# Qiao.net
KiCad netlist of a schematic drawn in Altium Designer
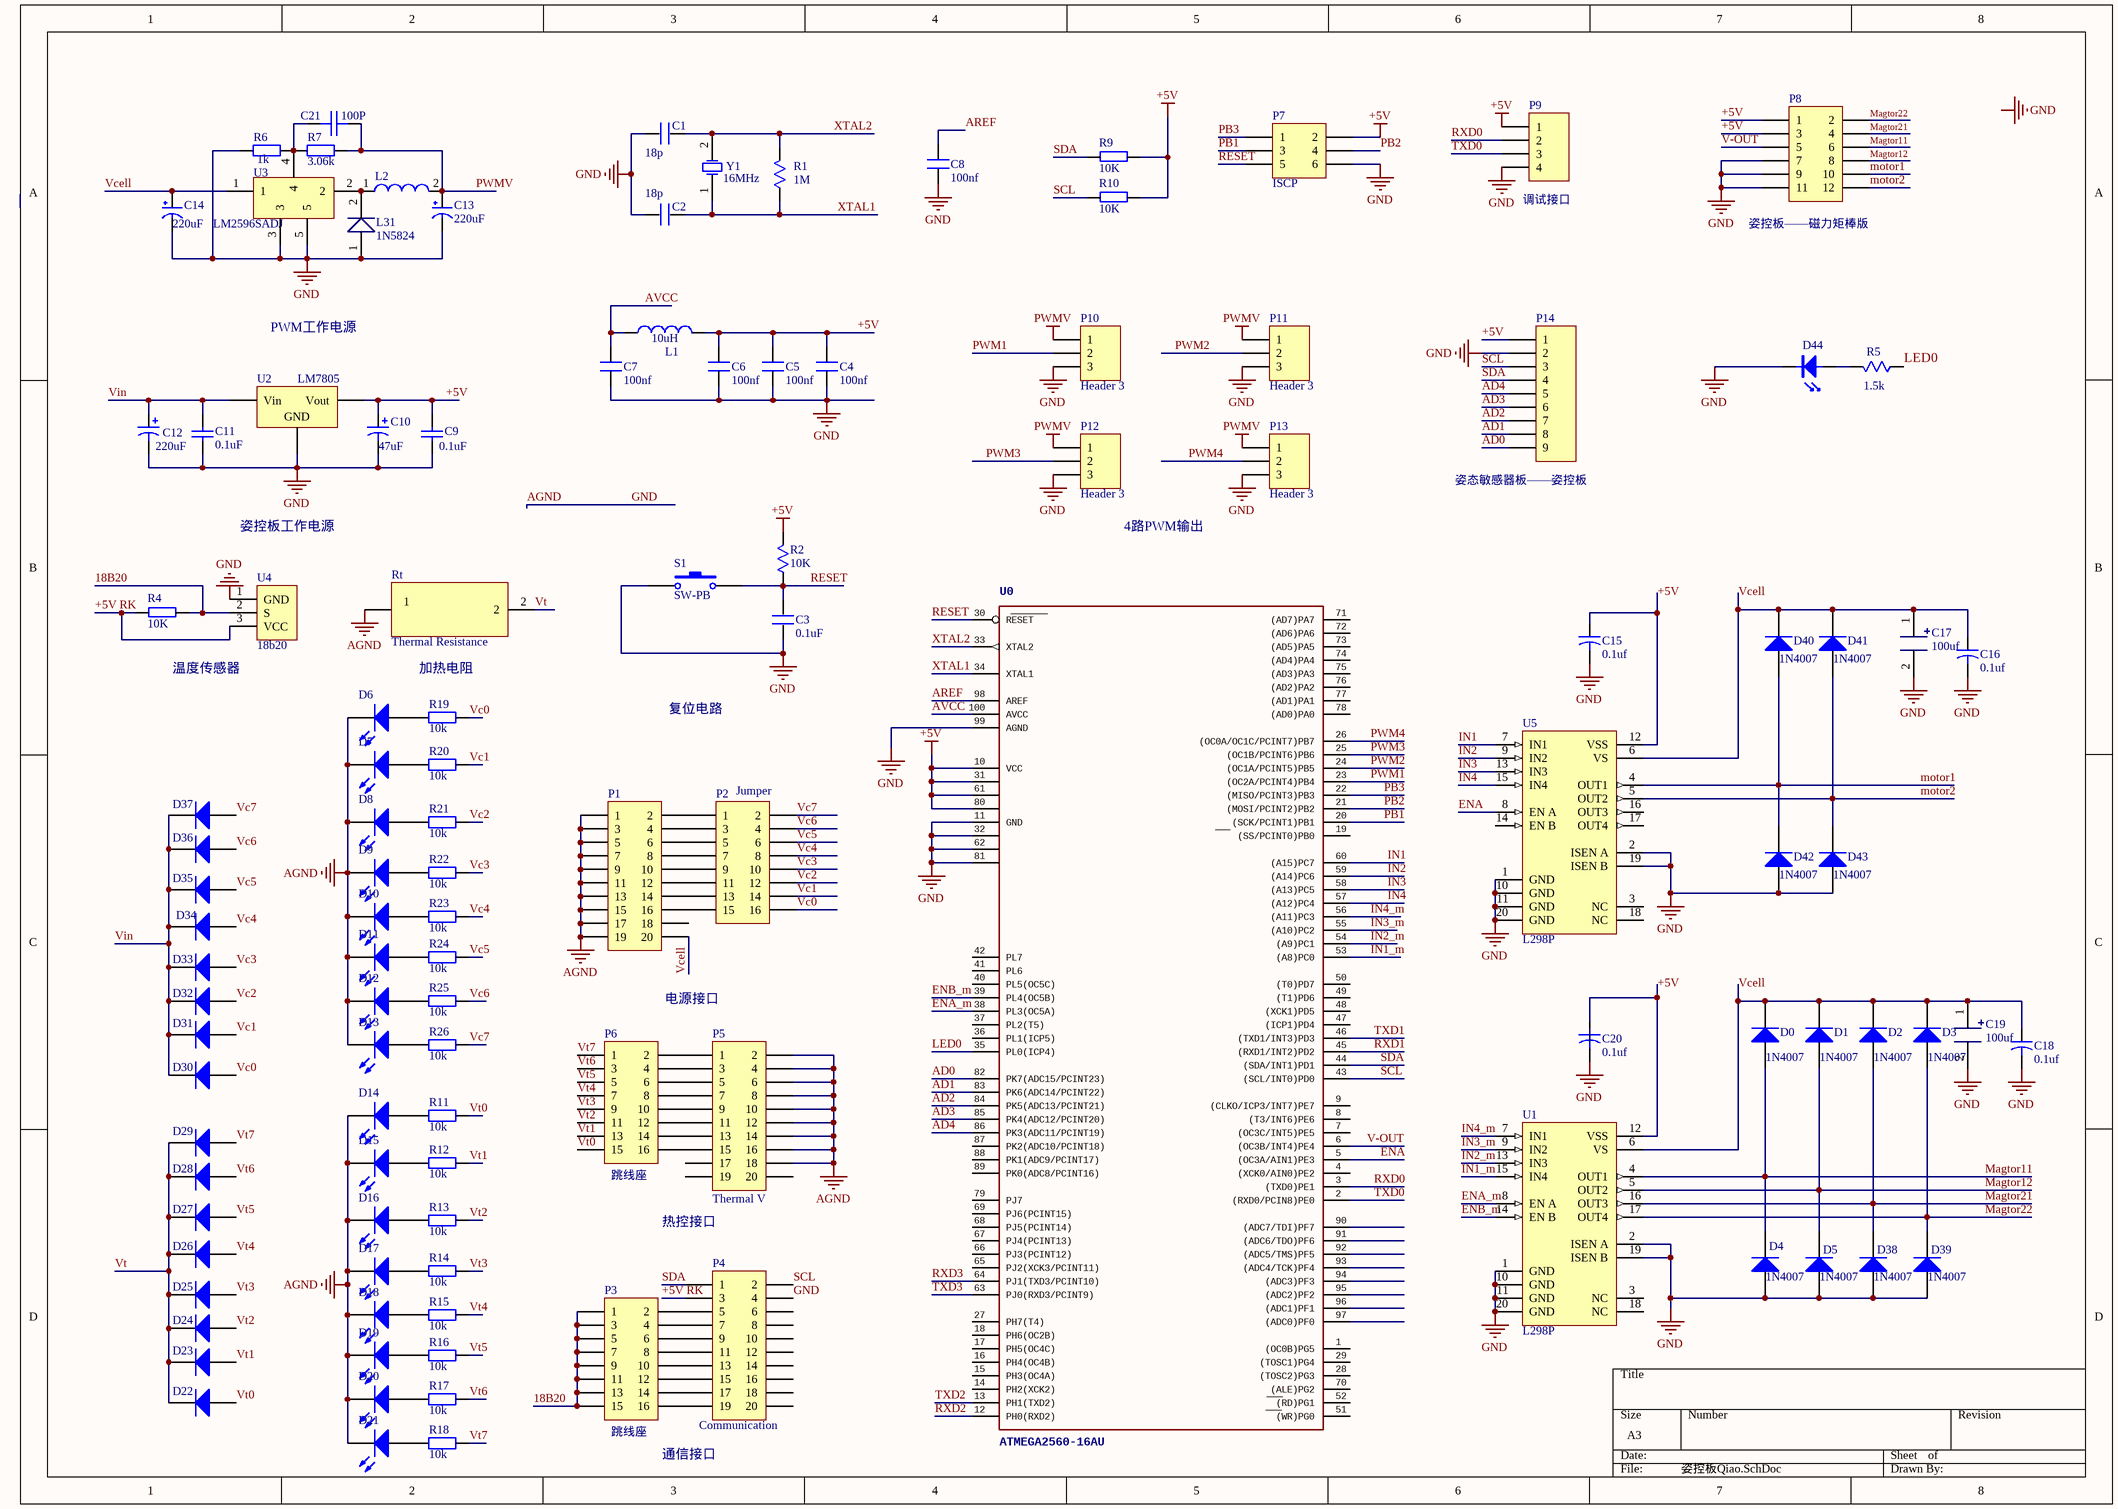
[diagram p0: 姿控板Qiao.SchDoc]

(export (version "E")
  (design (tool "Eeschema 10.0.6"))
  (components
    (comp (ref "C1") (value "18p") (footprint "CAPC3216M") (libsource (lib "STM32封装库") (part "C_1")))
    (comp (ref "C2") (value "18p") (footprint "CAPC3216M") (libsource (lib "STM32封装库") (part "C_1")))
    (comp (ref "C3") (value "0.1uF") (footprint "CAPC3216M") (libsource (lib "STM32封装库") (part "C_3")))
    (comp (ref "C4") (value "100nf") (footprint "CAPC3216M") (libsource (lib "STM32封装库") (part "C")))
    (comp (ref "C5") (value "100nf") (footprint "CAPC3216M") (libsource (lib "STM32封装库") (part "C")))
    (comp (ref "C6") (value "100nf") (footprint "CAPC3216M") (libsource (lib "STM32封装库") (part "C")))
    (comp (ref "C7") (value "100nf") (footprint "CAPC3216M") (libsource (lib "STM32封装库") (part "C")))
    (comp (ref "C8") (value "100nf") (footprint "CAPC3216M") (libsource (lib "STM32封装库") (part "C")))
    (comp (ref "C9")
      (value "0.1uF")
      (footprint "CAPC3216M")
      (description "0.1uf")
      (fields (field (name "PUBLISHER") "Altium Limited"))
      (libsource (lib "Miscellaneous Devices") (part "Cap Semi"))
    )
    (comp (ref "C10")
      (value "47uF")
      (footprint "25V47uF")
      (description "10uf")
      (fields (field (name "Comment") "25V47uF") (field (name "PUBLISHER") "Altium Limited"))
      (libsource (lib "Miscellaneous Devices") (part "Cap Pol3"))
    )
    (comp (ref "C11")
      (value "0.1uF")
      (footprint "CAPC3216M")
      (description "0.1uf")
      (fields (field (name "PUBLISHER") "Altium Limited"))
      (libsource (lib "Miscellaneous Devices") (part "Cap"))
    )
    (comp (ref "C12")
      (value "220uF")
      (footprint "25V47uF")
      (description "10uf")
      (fields (field (name "Comment") "50V220uF") (field (name "PUBLISHER") "Altium Limited"))
      (libsource (lib "Miscellaneous Devices") (part "Cap Pol3"))
    )
    (comp (ref "C13") (value "220uF") (footprint "25V47uF") (libsource (lib "STM32封装库") (part "CAP")))
    (comp (ref "C14") (value "220uF") (footprint "25V47uF") (libsource (lib "STM32封装库") (part "CAP")))
    (comp (ref "C15") (value "0.1uf") (footprint "25V47uF") (libsource (lib "常用元件库") (part "Cap_1")))
    (comp (ref "C16") (value "0.1uf") (footprint "25V47uF") (libsource (lib "常用元件库") (part "Cap_1")))
    (comp (ref "C17") (value "100uf") (footprint "CAPC3216M") (libsource (lib "capsmall") (part "capsmall")))
    (comp (ref "C18") (value "0.1uf") (footprint "25V47uF") (libsource (lib "常用元件库") (part "Cap_1")))
    (comp (ref "C19") (value "100uf") (footprint "CAPC3216M") (libsource (lib "capsmall") (part "capsmall")))
    (comp (ref "C20") (value "0.1uf") (footprint "25V47uF") (libsource (lib "常用元件库") (part "Cap_1")))
    (comp (ref "C21")
      (value "100P")
      (footprint "CAPC3216M")
      (description "100p")
      (libsource (lib "YT1_SCH_99SE") (part "CAP"))
    )
    (comp (ref "D0")
      (value "1N4007")
      (footprint "SMB")
      (description "1 Amp General Purpose Rectifier")
      (fields (field (name "PUBLISHER") "Altium Limited"))
      (libsource (lib "Miscellaneous Devices") (part "Diode 1N4007"))
    )
    (comp (ref "D1")
      (value "1N4007")
      (footprint "SMB")
      (description "1 Amp General Purpose Rectifier")
      (fields (field (name "PUBLISHER") "Altium Limited"))
      (libsource (lib "Miscellaneous Devices") (part "Diode 1N4007"))
    )
    (comp (ref "D2")
      (value "1N4007")
      (footprint "SMB")
      (description "1 Amp General Purpose Rectifier")
      (fields (field (name "PUBLISHER") "Altium Limited"))
      (libsource (lib "Miscellaneous Devices") (part "Diode 1N4007"))
    )
    (comp (ref "D3")
      (value "1N4007")
      (footprint "SMB")
      (description "1 Amp General Purpose Rectifier")
      (fields (field (name "PUBLISHER") "Altium Limited"))
      (libsource (lib "Miscellaneous Devices") (part "Diode 1N4007"))
    )
    (comp (ref "D4")
      (value "1N4007")
      (footprint "SMB")
      (description "1 Amp General Purpose Rectifier")
      (fields (field (name "PUBLISHER") "Altium Limited"))
      (libsource (lib "Miscellaneous Devices") (part "Diode 1N4007"))
    )
    (comp (ref "D5")
      (value "1N4007")
      (footprint "SMB")
      (description "1 Amp General Purpose Rectifier")
      (fields (field (name "PUBLISHER") "Altium Limited"))
      (libsource (lib "Miscellaneous Devices") (part "Diode 1N4007"))
    )
    (comp (ref "D6")
      (value "LED")
      (footprint "LED")
      (description "Typical RED, GREEN, YELLOW, AMBER GaAs LED")
      (fields (field (name "PUBLISHER") "Altium Limited"))
      (libsource (lib "Miscellaneous Devices") (part "LED2"))
    )
    (comp (ref "D7")
      (value "LED")
      (footprint "LED")
      (description "Typical RED, GREEN, YELLOW, AMBER GaAs LED")
      (fields (field (name "PUBLISHER") "Altium Limited"))
      (libsource (lib "Miscellaneous Devices") (part "LED2"))
    )
    (comp (ref "D8")
      (value "LED")
      (footprint "LED")
      (description "Typical RED, GREEN, YELLOW, AMBER GaAs LED")
      (fields (field (name "PUBLISHER") "Altium Limited"))
      (libsource (lib "Miscellaneous Devices") (part "LED2"))
    )
    (comp (ref "D9")
      (value "LED")
      (footprint "LED")
      (description "Typical RED, GREEN, YELLOW, AMBER GaAs LED")
      (fields (field (name "PUBLISHER") "Altium Limited"))
      (libsource (lib "Miscellaneous Devices") (part "LED2"))
    )
    (comp (ref "D10")
      (value "LED")
      (footprint "LED")
      (description "Typical RED, GREEN, YELLOW, AMBER GaAs LED")
      (fields (field (name "PUBLISHER") "Altium Limited"))
      (libsource (lib "Miscellaneous Devices") (part "LED2"))
    )
    (comp (ref "D11")
      (value "LED")
      (footprint "LED")
      (description "Typical RED, GREEN, YELLOW, AMBER GaAs LED")
      (fields (field (name "PUBLISHER") "Altium Limited"))
      (libsource (lib "Miscellaneous Devices") (part "LED2"))
    )
    (comp (ref "D12")
      (value "LED")
      (footprint "LED")
      (description "Typical RED, GREEN, YELLOW, AMBER GaAs LED")
      (fields (field (name "PUBLISHER") "Altium Limited"))
      (libsource (lib "Miscellaneous Devices") (part "LED2"))
    )
    (comp (ref "D13")
      (value "LED")
      (footprint "LED")
      (description "Typical RED, GREEN, YELLOW, AMBER GaAs LED")
      (fields (field (name "PUBLISHER") "Altium Limited"))
      (libsource (lib "Miscellaneous Devices") (part "LED2"))
    )
    (comp (ref "D14")
      (value "LED")
      (footprint "LED")
      (description "Typical RED, GREEN, YELLOW, AMBER GaAs LED")
      (fields (field (name "PUBLISHER") "Altium Limited"))
      (libsource (lib "Miscellaneous Devices") (part "LED2"))
    )
    (comp (ref "D15")
      (value "LED")
      (footprint "LED")
      (description "Typical RED, GREEN, YELLOW, AMBER GaAs LED")
      (fields (field (name "PUBLISHER") "Altium Limited"))
      (libsource (lib "Miscellaneous Devices") (part "LED2"))
    )
    (comp (ref "D16")
      (value "LED")
      (footprint "LED")
      (description "Typical RED, GREEN, YELLOW, AMBER GaAs LED")
      (fields (field (name "PUBLISHER") "Altium Limited"))
      (libsource (lib "Miscellaneous Devices") (part "LED2"))
    )
    (comp (ref "D17")
      (value "LED")
      (footprint "LED")
      (description "Typical RED, GREEN, YELLOW, AMBER GaAs LED")
      (fields (field (name "PUBLISHER") "Altium Limited"))
      (libsource (lib "Miscellaneous Devices") (part "LED2"))
    )
    (comp (ref "D18")
      (value "LED")
      (footprint "LED")
      (description "Typical RED, GREEN, YELLOW, AMBER GaAs LED")
      (fields (field (name "PUBLISHER") "Altium Limited"))
      (libsource (lib "Miscellaneous Devices") (part "LED2"))
    )
    (comp (ref "D19")
      (value "LED")
      (footprint "LED")
      (description "Typical RED, GREEN, YELLOW, AMBER GaAs LED")
      (fields (field (name "PUBLISHER") "Altium Limited"))
      (libsource (lib "Miscellaneous Devices") (part "LED2"))
    )
    (comp (ref "D20")
      (value "LED")
      (footprint "LED")
      (description "Typical RED, GREEN, YELLOW, AMBER GaAs LED")
      (fields (field (name "PUBLISHER") "Altium Limited"))
      (libsource (lib "Miscellaneous Devices") (part "LED2"))
    )
    (comp (ref "D21")
      (value "LED")
      (footprint "LED")
      (description "Typical RED, GREEN, YELLOW, AMBER GaAs LED")
      (fields (field (name "PUBLISHER") "Altium Limited"))
      (libsource (lib "Miscellaneous Devices") (part "LED2"))
    )
    (comp (ref "D22")
      (value "1N4001")
      (footprint "SMB")
      (description "1 Amp General Purpose Rectifier")
      (fields (field (name "PUBLISHER") "Altium Limited"))
      (libsource (lib "Miscellaneous Devices") (part "Diode 1N4001"))
    )
    (comp (ref "D23")
      (value "1N4001")
      (footprint "SMB")
      (description "1 Amp General Purpose Rectifier")
      (fields (field (name "PUBLISHER") "Altium Limited"))
      (libsource (lib "Miscellaneous Devices") (part "Diode 1N4001"))
    )
    (comp (ref "D24")
      (value "1N4001")
      (footprint "SMB")
      (description "1 Amp General Purpose Rectifier")
      (fields (field (name "PUBLISHER") "Altium Limited"))
      (libsource (lib "Miscellaneous Devices") (part "Diode 1N4001"))
    )
    (comp (ref "D25")
      (value "1N4001")
      (footprint "SMB")
      (description "1 Amp General Purpose Rectifier")
      (fields (field (name "PUBLISHER") "Altium Limited"))
      (libsource (lib "Miscellaneous Devices") (part "Diode 1N4001"))
    )
    (comp (ref "D26")
      (value "1N4001")
      (footprint "SMB")
      (description "1 Amp General Purpose Rectifier")
      (fields (field (name "PUBLISHER") "Altium Limited"))
      (libsource (lib "Miscellaneous Devices") (part "Diode 1N4001"))
    )
    (comp (ref "D27")
      (value "1N4001")
      (footprint "SMB")
      (description "1 Amp General Purpose Rectifier")
      (fields (field (name "PUBLISHER") "Altium Limited"))
      (libsource (lib "Miscellaneous Devices") (part "Diode 1N4001"))
    )
    (comp (ref "D28")
      (value "1N4001")
      (footprint "SMB")
      (description "1 Amp General Purpose Rectifier")
      (fields (field (name "PUBLISHER") "Altium Limited"))
      (libsource (lib "Miscellaneous Devices") (part "Diode 1N4001"))
    )
    (comp (ref "D29")
      (value "1N4001")
      (footprint "SMB")
      (description "1 Amp General Purpose Rectifier")
      (fields (field (name "PUBLISHER") "Altium Limited"))
      (libsource (lib "Miscellaneous Devices") (part "Diode 1N4001"))
    )
    (comp (ref "D30")
      (value "1N4001")
      (footprint "SMB")
      (description "1 Amp General Purpose Rectifier")
      (fields (field (name "PUBLISHER") "Altium Limited"))
      (libsource (lib "Miscellaneous Devices") (part "Diode 1N4001"))
    )
    (comp (ref "D31")
      (value "1N4001")
      (footprint "SMB")
      (description "1 Amp General Purpose Rectifier")
      (fields (field (name "PUBLISHER") "Altium Limited"))
      (libsource (lib "Miscellaneous Devices") (part "Diode 1N4001"))
    )
    (comp (ref "D32")
      (value "1N4001")
      (footprint "SMB")
      (description "1 Amp General Purpose Rectifier")
      (fields (field (name "PUBLISHER") "Altium Limited"))
      (libsource (lib "Miscellaneous Devices") (part "Diode 1N4001"))
    )
    (comp (ref "D33")
      (value "1N4001")
      (footprint "SMB")
      (description "1 Amp General Purpose Rectifier")
      (fields (field (name "PUBLISHER") "Altium Limited"))
      (libsource (lib "Miscellaneous Devices") (part "Diode 1N4001"))
    )
    (comp (ref "D34")
      (value "1N4001")
      (footprint "SMB")
      (description "1 Amp General Purpose Rectifier")
      (fields (field (name "PUBLISHER") "Altium Limited"))
      (libsource (lib "Miscellaneous Devices") (part "Diode 1N4001"))
    )
    (comp (ref "D35")
      (value "1N4001")
      (footprint "SMB")
      (description "1 Amp General Purpose Rectifier")
      (fields (field (name "PUBLISHER") "Altium Limited"))
      (libsource (lib "Miscellaneous Devices") (part "Diode 1N4001"))
    )
    (comp (ref "D36")
      (value "1N4001")
      (footprint "SMB")
      (description "1 Amp General Purpose Rectifier")
      (fields (field (name "PUBLISHER") "Altium Limited"))
      (libsource (lib "Miscellaneous Devices") (part "Diode 1N4001"))
    )
    (comp (ref "D37")
      (value "1N4001")
      (footprint "SMB")
      (description "1 Amp General Purpose Rectifier")
      (fields (field (name "PUBLISHER") "Altium Limited"))
      (libsource (lib "Miscellaneous Devices") (part "Diode 1N4001"))
    )
    (comp (ref "D38")
      (value "1N4007")
      (footprint "SMB")
      (description "1 Amp General Purpose Rectifier")
      (fields (field (name "PUBLISHER") "Altium Limited"))
      (libsource (lib "Miscellaneous Devices") (part "Diode 1N4007"))
    )
    (comp (ref "D39")
      (value "1N4007")
      (footprint "SMB")
      (description "1 Amp General Purpose Rectifier")
      (fields (field (name "PUBLISHER") "Altium Limited"))
      (libsource (lib "Miscellaneous Devices") (part "Diode 1N4007"))
    )
    (comp (ref "D40")
      (value "1N4007")
      (footprint "SMB")
      (description "1 Amp General Purpose Rectifier")
      (fields (field (name "PUBLISHER") "Altium Limited"))
      (libsource (lib "Miscellaneous Devices") (part "Diode 1N4007"))
    )
    (comp (ref "D41")
      (value "1N4007")
      (footprint "SMB")
      (description "1 Amp General Purpose Rectifier")
      (fields (field (name "PUBLISHER") "Altium Limited"))
      (libsource (lib "Miscellaneous Devices") (part "Diode 1N4007"))
    )
    (comp (ref "D42")
      (value "1N4007")
      (footprint "SMB")
      (description "1 Amp General Purpose Rectifier")
      (fields (field (name "PUBLISHER") "Altium Limited"))
      (libsource (lib "Miscellaneous Devices") (part "Diode 1N4007"))
    )
    (comp (ref "D43")
      (value "1N4007")
      (footprint "SMB")
      (description "1 Amp General Purpose Rectifier")
      (fields (field (name "PUBLISHER") "Altium Limited"))
      (libsource (lib "Miscellaneous Devices") (part "Diode 1N4007"))
    )
    (comp (ref "D44") (value "DS0") (footprint "常用元件封装:LED") (libsource (lib "YT1_SCH_99SE") (part "LED")))
    (comp (ref "L1")
      (value "10uH")
      (footprint "CAPC3216M")
      (description "Inductor")
      (fields (field (name "PUBLISHER") "Altium Limited"))
      (libsource (lib "Miscellaneous Devices") (part "Inductor"))
    )
    (comp (ref "L2")
      (value "inductance")
      (footprint "INDUCTANCE_1")
      (libsource (lib "STM32封装库") (part "inductance"))
    )
    (comp (ref "L31") (value "1N5824") (footprint "DO214AC") (libsource (lib "STM32封装库") (part "1N5824")))
    (comp (ref "P1")
      (value "Power Interface")
      (footprint "HDR2X10")
      (description "Header, 10-Pin, Dual row")
      (fields (field (name "PUBLISHER") "Altium Limited"))
      (libsource (lib "Miscellaneous Connectors") (part "Header 10X2"))
    )
    (comp (ref "P2")
      (value "Jumper")
      (footprint "HDR2X8")
      (description "Header, 8-Pin, Dual row")
      (fields (field (name "PUBLISHER") "Altium Limited"))
      (libsource (lib "Miscellaneous Connectors") (part "Header 8X2"))
    )
    (comp (ref "P3")
      (value "跳线座")
      (footprint "HDR2X8")
      (description "Header, 8-Pin, Dual row")
      (fields (field (name "PUBLISHER") "Altium Limited"))
      (libsource (lib "Miscellaneous Connectors") (part "Header 8X2"))
    )
    (comp (ref "P4")
      (value "Communication")
      (footprint "HDR2X10")
      (description "Header, 10-Pin, Dual row")
      (fields (field (name "PUBLISHER") "Altium Limited"))
      (libsource (lib "Miscellaneous Connectors") (part "Header 10X2"))
    )
    (comp (ref "P5")
      (value "Thermal V")
      (footprint "HDR2X10")
      (description "Header, 10-Pin, Dual row")
      (fields (field (name "PUBLISHER") "Altium Limited"))
      (libsource (lib "Miscellaneous Connectors") (part "Header 10X2"))
    )
    (comp (ref "P6")
      (value "跳线座")
      (footprint "HDR2X8")
      (description "Header, 8-Pin, Dual row")
      (fields (field (name "PUBLISHER") "Altium Limited"))
      (libsource (lib "Miscellaneous Connectors") (part "Header 8X2"))
    )
    (comp (ref "P7")
      (value "ISCP")
      (footprint "HDR2X3")
      (description "Header, 3-Pin, Dual row")
      (fields (field (name "PUBLISHER") "Altium Limited"))
      (libsource (lib "Miscellaneous Connectors") (part "Header 3X2"))
    )
    (comp (ref "P8")
      (value "姿控板——磁力矩棒版")
      (footprint "HDR2X6")
      (description "Header, 6-Pin, Dual row")
      (fields (field (name "PUBLISHER") "Altium Limited"))
      (libsource (lib "Miscellaneous Connectors") (part "Header 6X2"))
    )
    (comp (ref "P9")
      (value "调试接口")
      (footprint "HDR1X4")
      (description "Header, 4-Pin")
      (fields (field (name "PUBLISHER") "Altium Limited"))
      (libsource (lib "Miscellaneous Connectors") (part "Header 4"))
    )
    (comp (ref "P10")
      (value "Header 3")
      (footprint "HDR1X3")
      (description "Header, 3-Pin")
      (fields (field (name "PUBLISHER") "Altium Limited"))
      (libsource (lib "Miscellaneous Connectors") (part "Header 3"))
    )
    (comp (ref "P11")
      (value "Header 3")
      (footprint "HDR1X3")
      (description "Header, 3-Pin")
      (fields (field (name "PUBLISHER") "Altium Limited"))
      (libsource (lib "Miscellaneous Connectors") (part "Header 3"))
    )
    (comp (ref "P12")
      (value "Header 3")
      (footprint "HDR1X3")
      (description "Header, 3-Pin")
      (fields (field (name "PUBLISHER") "Altium Limited"))
      (libsource (lib "Miscellaneous Connectors") (part "Header 3"))
    )
    (comp (ref "P13")
      (value "Header 3")
      (footprint "HDR1X3")
      (description "Header, 3-Pin")
      (fields (field (name "PUBLISHER") "Altium Limited"))
      (libsource (lib "Miscellaneous Connectors") (part "Header 3"))
    )
    (comp (ref "P14")
      (value "姿态敏感器板——姿控板")
      (footprint "HDR1X9")
      (description "Header, 9-Pin")
      (fields (field (name "PUBLISHER") "Altium Limited"))
      (libsource (lib "Miscellaneous Connectors") (part "Header 9"))
    )
    (comp (ref "R1") (value "1M") (footprint "RESC3216M") (libsource (lib "YT1_SCH_99SE") (part "RES")))
    (comp (ref "R2") (value "10K") (footprint "RESC3216M") (libsource (lib "YT1_SCH_99SE") (part "RES")))
    (comp (ref "R4") (value "10K") (footprint "RESC3216M") (libsource (lib "STM32封装库") (part "R")))
    (comp (ref "R5") (value "1.5k") (footprint "RESC3216m") (libsource (lib "YT1_SCH_99SE") (part "RES")))
    (comp (ref "R6")
      (value "1k")
      (footprint "RESC3216M")
      (description "Resistor")
      (fields (field (name "PUBLISHER") "Altium Limited"))
      (libsource (lib "") (part "Res2_1"))
    )
    (comp (ref "R7")
      (value "3.06k")
      (footprint "RESC3216M")
      (description "Resistor")
      (fields (field (name "Comment") "5.1k") (field (name "PUBLISHER") "Altium Limited"))
      (libsource (lib "") (part "Res2_1"))
    )
    (comp (ref "R9") (value "10K") (footprint "RESC3216M") (libsource (lib "STM32封装库") (part "R")))
    (comp (ref "R10") (value "10K") (footprint "RESC3216M") (libsource (lib "STM32封装库") (part "R")))
    (comp (ref "R11")
      (value "10k")
      (footprint "RESC3216M")
      (description "5.1k")
      (fields (field (name "Comment") "10K") (field (name "PUBLISHER") "Altium Limited"))
      (libsource (lib "Miscellaneous Devices") (part "Res2"))
    )
    (comp (ref "R12")
      (value "10k")
      (footprint "RESC3216M")
      (description "5.1k")
      (fields (field (name "Comment") "10K") (field (name "PUBLISHER") "Altium Limited"))
      (libsource (lib "Miscellaneous Devices") (part "Res2"))
    )
    (comp (ref "R13")
      (value "10k")
      (footprint "RESC3216M")
      (description "5.1k")
      (fields (field (name "Comment") "10K") (field (name "PUBLISHER") "Altium Limited"))
      (libsource (lib "Miscellaneous Devices") (part "Res2"))
    )
    (comp (ref "R14")
      (value "10k")
      (footprint "RESC3216M")
      (description "5.1k")
      (fields (field (name "Comment") "10K") (field (name "PUBLISHER") "Altium Limited"))
      (libsource (lib "Miscellaneous Devices") (part "Res2"))
    )
    (comp (ref "R15")
      (value "10k")
      (footprint "RESC3216M")
      (description "5.1k")
      (fields (field (name "Comment") "10K") (field (name "PUBLISHER") "Altium Limited"))
      (libsource (lib "Miscellaneous Devices") (part "Res2"))
    )
    (comp (ref "R16")
      (value "10k")
      (footprint "RESC3216M")
      (description "5.1k")
      (fields (field (name "Comment") "10K") (field (name "PUBLISHER") "Altium Limited"))
      (libsource (lib "Miscellaneous Devices") (part "Res2"))
    )
    (comp (ref "R17")
      (value "10k")
      (footprint "RESC3216M")
      (description "5.1k")
      (fields (field (name "Comment") "10K") (field (name "PUBLISHER") "Altium Limited"))
      (libsource (lib "Miscellaneous Devices") (part "Res2"))
    )
    (comp (ref "R18")
      (value "10k")
      (footprint "RESC3216M")
      (description "5.1k")
      (fields (field (name "Comment") "10K") (field (name "PUBLISHER") "Altium Limited"))
      (libsource (lib "Miscellaneous Devices") (part "Res2"))
    )
    (comp (ref "R19")
      (value "10k")
      (footprint "RESC3216M")
      (description "5.1k")
      (fields (field (name "Comment") "10K") (field (name "PUBLISHER") "Altium Limited"))
      (libsource (lib "Miscellaneous Devices") (part "Res2"))
    )
    (comp (ref "R20")
      (value "10k")
      (footprint "RESC3216M")
      (description "5.1k")
      (fields (field (name "Comment") "10K") (field (name "PUBLISHER") "Altium Limited"))
      (libsource (lib "Miscellaneous Devices") (part "Res2"))
    )
    (comp (ref "R21")
      (value "10k")
      (footprint "RESC3216M")
      (description "5.1k")
      (fields (field (name "Comment") "10K") (field (name "PUBLISHER") "Altium Limited"))
      (libsource (lib "Miscellaneous Devices") (part "Res2"))
    )
    (comp (ref "R22")
      (value "10k")
      (footprint "RESC3216M")
      (description "5.1k")
      (fields (field (name "Comment") "10K") (field (name "PUBLISHER") "Altium Limited"))
      (libsource (lib "Miscellaneous Devices") (part "Res2"))
    )
    (comp (ref "R23")
      (value "10k")
      (footprint "RESC3216M")
      (description "5.1k")
      (fields (field (name "Comment") "10K") (field (name "PUBLISHER") "Altium Limited"))
      (libsource (lib "Miscellaneous Devices") (part "Res2"))
    )
    (comp (ref "R24")
      (value "10k")
      (footprint "RESC3216M")
      (description "5.1k")
      (fields (field (name "Comment") "10K") (field (name "PUBLISHER") "Altium Limited"))
      (libsource (lib "Miscellaneous Devices") (part "Res2"))
    )
    (comp (ref "R25")
      (value "10k")
      (footprint "RESC3216M")
      (description "5.1k")
      (fields (field (name "Comment") "10K") (field (name "PUBLISHER") "Altium Limited"))
      (libsource (lib "Miscellaneous Devices") (part "Res2"))
    )
    (comp (ref "R26")
      (value "10k")
      (footprint "RESC3216M")
      (description "5.1k")
      (fields (field (name "Comment") "10K") (field (name "PUBLISHER") "Altium Limited"))
      (libsource (lib "Miscellaneous Devices") (part "Res2"))
    )
    (comp (ref "Rt")
      (value "Thermal Resistance")
      (footprint "Thermal Res")
      (libsource (lib "MyFootprintLibrary") (part "ThermalResistance"))
    )
    (comp (ref "S1")
      (value "SW-PB")
      (footprint "PUSH BUTTON 6x6")
      (description "Switch")
      (fields (field (name "PUBLISHER") "Altium Limited"))
      (libsource (lib "Miscellaneous Devices") (part "SW-PB"))
    )
    (comp (ref "U0")
      (value "ATMEGA2560-16AU")
      (footprint "TQFP100")
      (libsource (lib "Arduino_MEGA_2560-Rev3") (part "ATMEGA2560AU"))
    )
    (comp (ref "U1")
      (value "L298P")
      (footprint "PowerSO20_N")
      (description "Dual Full Bridge Driver")
      (fields (field (name "PUBLISHER") "Altium Limited"))
      (libsource (lib "ST Interface DC Motor Controller") (part "L298P"))
    )
    (comp (ref "U2")
      (value "LM7805")
      (footprint "DPAK-3")
      (description "Voltage Regulator")
      (fields (field (name "PUBLISHER") "Altium Limited"))
      (libsource (lib "Miscellaneous Devices") (part "Volt Reg"))
    )
    (comp (ref "U3")
      (value "LM2596SADJ")
      (footprint "TO263_5")
      (libsource (lib "STM32封装库") (part "LM2596SADJ"))
    )
    (comp (ref "U4") (value "18b20") (footprint "TO92") (libsource (lib "常用元件库") (part "18b20")))
    (comp (ref "U5")
      (value "L298P")
      (footprint "PowerSO20_N")
      (description "Dual Full Bridge Driver")
      (fields (field (name "PUBLISHER") "Altium Limited"))
      (libsource (lib "ST Interface DC Motor Controller") (part "L298P"))
    )
    (comp (ref "Y1")
      (value "16MHz")
      (footprint "XTAL_US")
      (description "Crystal Oscillator")
      (fields (field (name "PUBLISHER") "Altium Limited"))
      (libsource (lib "电源管理板") (part "XTAL"))
    )
  )
  (nets
    (net (code "1") (name "+5V") (class "Default")
      (node (ref "C10") (pin "1") (pinfunction "1_1") (pintype "passive"))
      (node (ref "C15") (pin "1") (pinfunction "1_1") (pintype "passive"))
      (node (ref "C20") (pin "1") (pinfunction "1_1") (pintype "passive"))
      (node (ref "C4") (pin "2") (pintype "passive"))
      (node (ref "C5") (pin "2") (pintype "passive"))
      (node (ref "C6") (pin "2") (pintype "passive"))
      (node (ref "C9") (pin "2") (pinfunction "2_2") (pintype "passive"))
      (node (ref "L1") (pin "2") (pinfunction "2_2") (pintype "passive"))
      (node (ref "P14") (pin "1") (pinfunction "1_1") (pintype "passive"))
      (node (ref "P7") (pin "2") (pinfunction "2_2") (pintype "passive"))
      (node (ref "P8") (pin "1") (pinfunction "1_1") (pintype "passive"))
      (node (ref "P8") (pin "3") (pinfunction "3_3") (pintype "passive"))
      (node (ref "P9") (pin "1") (pinfunction "1_1") (pintype "passive"))
      (node (ref "R10") (pin "1") (pintype "passive"))
      (node (ref "R2") (pin "2") (pinfunction "2_2") (pintype "passive"))
      (node (ref "R9") (pin "1") (pintype "passive"))
      (node (ref "U0") (pin "10") (pinfunction "VCC_10") (pintype "power_in"))
      (node (ref "U0") (pin "31") (pinfunction "VCC1_31") (pintype "power_in"))
      (node (ref "U0") (pin "61") (pinfunction "VCC2_61") (pintype "power_in"))
      (node (ref "U0") (pin "80") (pinfunction "VCC3_80") (pintype "power_in"))
      (node (ref "U1") (pin "12") (pinfunction "VSS_12") (pintype "power_in"))
      (node (ref "U2") (pin "3") (pinfunction "Vout_3") (pintype "passive"))
      (node (ref "U5") (pin "12") (pinfunction "VSS_12") (pintype "power_in"))
    )
    (net (code "2") (name "/+5V RK") (class "Default")
      (node (ref "P4") (pin "3") (pinfunction "3_3") (pintype "passive"))
      (node (ref "R4") (pin "2") (pintype "passive"))
      (node (ref "U4") (pin "3") (pinfunction "VCC_3") (pintype "passive"))
    )
    (net (code "3") (name "/18B20") (class "Default")
      (node (ref "P3") (pin "1") (pinfunction "1_1") (pintype "passive"))
      (node (ref "P3") (pin "11") (pinfunction "11_11") (pintype "passive"))
      (node (ref "P3") (pin "13") (pinfunction "13_13") (pintype "passive"))
      (node (ref "P3") (pin "15") (pinfunction "15_15") (pintype "passive"))
      (node (ref "P3") (pin "3") (pinfunction "3_3") (pintype "passive"))
      (node (ref "P3") (pin "5") (pinfunction "5_5") (pintype "passive"))
      (node (ref "P3") (pin "7") (pinfunction "7_7") (pintype "passive"))
      (node (ref "P3") (pin "9") (pinfunction "9_9") (pintype "passive"))
      (node (ref "R4") (pin "1") (pintype "passive"))
      (node (ref "U4") (pin "2") (pinfunction "S_2") (pintype "passive"))
    )
    (net (code "4") (name "/AD0") (class "Default")
      (node (ref "P14") (pin "9") (pinfunction "9_9") (pintype "passive"))
      (node (ref "U0") (pin "82") (pinfunction "PK7(ADC15/PCINT23)_82") (pintype "passive"))
    )
    (net (code "5") (name "/AD1") (class "Default")
      (node (ref "P14") (pin "8") (pinfunction "8_8") (pintype "passive"))
      (node (ref "U0") (pin "83") (pinfunction "PK6(ADC14/PCINT22)_83") (pintype "passive"))
    )
    (net (code "6") (name "/AD2") (class "Default")
      (node (ref "P14") (pin "7") (pinfunction "7_7") (pintype "passive"))
      (node (ref "U0") (pin "84") (pinfunction "PK5(ADC13/PCINT21)_84") (pintype "passive"))
    )
    (net (code "7") (name "/AD3") (class "Default")
      (node (ref "P14") (pin "6") (pinfunction "6_6") (pintype "passive"))
      (node (ref "U0") (pin "85") (pinfunction "PK4(ADC12/PCINT20)_85") (pintype "passive"))
    )
    (net (code "8") (name "/AD4") (class "Default")
      (node (ref "P14") (pin "5") (pinfunction "5_5") (pintype "passive"))
      (node (ref "U0") (pin "86") (pinfunction "PK3(ADC11/PCINT19)_86") (pintype "passive"))
    )
    (net (code "9") (name "/AREF") (class "Default")
      (node (ref "C8") (pin "2") (pintype "passive"))
      (node (ref "U0") (pin "98") (pinfunction "AREF_98") (pintype "passive"))
    )
    (net (code "10") (name "/AVCC") (class "Default")
      (node (ref "C7") (pin "2") (pintype "passive"))
      (node (ref "L1") (pin "1") (pinfunction "1_1") (pintype "passive"))
      (node (ref "U0") (pin "100") (pinfunction "AVCC_100") (pintype "power_in"))
    )
    (net (code "11") (name "/ENA") (class "Default")
      (node (ref "U0") (pin "5") (pinfunction "(OC3A/AIN1)PE3_5") (pintype "passive"))
      (node (ref "U5") (pin "8") (pinfunction "EN_A_8") (pintype "input"))
    )
    (net (code "12") (name "/ENA_m") (class "Default")
      (node (ref "U0") (pin "38") (pinfunction "PL3(OC5A)_38") (pintype "passive"))
      (node (ref "U1") (pin "8") (pinfunction "EN_A_8") (pintype "input"))
    )
    (net (code "13") (name "/ENB_m") (class "Default")
      (node (ref "U0") (pin "39") (pinfunction "PL4(OC5B)_39") (pintype "passive"))
      (node (ref "U1") (pin "14") (pinfunction "EN_B_14") (pintype "input"))
    )
    (net (code "14") (name "/IN1") (class "Default")
      (node (ref "U0") (pin "60") (pinfunction "(A15)PC7_60") (pintype "passive"))
      (node (ref "U5") (pin "7") (pinfunction "IN1_7") (pintype "input"))
    )
    (net (code "15") (name "/IN1_m") (class "Default")
      (node (ref "U0") (pin "53") (pinfunction "(A8)PC0_53") (pintype "passive"))
      (node (ref "U1") (pin "15") (pinfunction "IN4_15") (pintype "input"))
    )
    (net (code "16") (name "/IN2") (class "Default")
      (node (ref "U0") (pin "59") (pinfunction "(A14)PC6_59") (pintype "passive"))
      (node (ref "U5") (pin "9") (pinfunction "IN2_9") (pintype "input"))
    )
    (net (code "17") (name "/IN2_m") (class "Default")
      (node (ref "U0") (pin "54") (pinfunction "(A9)PC1_54") (pintype "passive"))
      (node (ref "U1") (pin "13") (pinfunction "IN3_13") (pintype "input"))
    )
    (net (code "18") (name "/IN3") (class "Default")
      (node (ref "U0") (pin "58") (pinfunction "(A13)PC5_58") (pintype "passive"))
      (node (ref "U5") (pin "13") (pinfunction "IN3_13") (pintype "input"))
    )
    (net (code "19") (name "/IN3_m") (class "Default")
      (node (ref "U0") (pin "55") (pinfunction "(A10)PC2_55") (pintype "passive"))
      (node (ref "U1") (pin "9") (pinfunction "IN2_9") (pintype "input"))
    )
    (net (code "20") (name "/IN4") (class "Default")
      (node (ref "U0") (pin "57") (pinfunction "(A12)PC4_57") (pintype "passive"))
      (node (ref "U5") (pin "15") (pinfunction "IN4_15") (pintype "input"))
    )
    (net (code "21") (name "/IN4_m") (class "Default")
      (node (ref "U0") (pin "56") (pinfunction "(A11)PC3_56") (pintype "passive"))
      (node (ref "U1") (pin "7") (pinfunction "IN1_7") (pintype "input"))
    )
    (net (code "22") (name "/LED0") (class "Default")
      (node (ref "R5") (pin "1") (pinfunction "1_1") (pintype "passive"))
      (node (ref "U0") (pin "35") (pinfunction "PL0(ICP4)_35") (pintype "passive"))
    )
    (net (code "23") (name "/Magtor11") (class "Default")
      (node (ref "D0") (pin "1") (pinfunction "A_1") (pintype "passive"))
      (node (ref "D4") (pin "2") (pinfunction "K_2") (pintype "passive"))
      (node (ref "P8") (pin "6") (pinfunction "6_6") (pintype "passive"))
      (node (ref "U1") (pin "4") (pinfunction "OUT1_4") (pintype "output"))
    )
    (net (code "24") (name "/Magtor12") (class "Default")
      (node (ref "D1") (pin "1") (pinfunction "A_1") (pintype "passive"))
      (node (ref "D5") (pin "2") (pinfunction "K_2") (pintype "passive"))
      (node (ref "P8") (pin "8") (pinfunction "8_8") (pintype "passive"))
      (node (ref "U1") (pin "5") (pinfunction "OUT2_5") (pintype "output"))
    )
    (net (code "25") (name "/Magtor21") (class "Default")
      (node (ref "D2") (pin "1") (pinfunction "A_1") (pintype "passive"))
      (node (ref "D38") (pin "2") (pinfunction "K_2") (pintype "passive"))
      (node (ref "P8") (pin "4") (pinfunction "4_4") (pintype "passive"))
      (node (ref "U1") (pin "16") (pinfunction "OUT3_16") (pintype "output"))
    )
    (net (code "26") (name "/Magtor22") (class "Default")
      (node (ref "D3") (pin "1") (pinfunction "A_1") (pintype "passive"))
      (node (ref "D39") (pin "2") (pinfunction "K_2") (pintype "passive"))
      (node (ref "P8") (pin "2") (pinfunction "2_2") (pintype "passive"))
      (node (ref "U1") (pin "17") (pinfunction "OUT4_17") (pintype "output"))
    )
    (net (code "27") (name "/PB1") (class "Default")
      (node (ref "P7") (pin "3") (pinfunction "3_3") (pintype "passive"))
      (node (ref "U0") (pin "20") (pinfunction "(SCK/PCINT1)PB1_20") (pintype "passive"))
    )
    (net (code "28") (name "/PB2") (class "Default")
      (node (ref "P7") (pin "4") (pinfunction "4_4") (pintype "passive"))
      (node (ref "U0") (pin "21") (pinfunction "(MOSI/PCINT2)PB2_21") (pintype "passive"))
    )
    (net (code "29") (name "/PB3") (class "Default")
      (node (ref "P7") (pin "1") (pinfunction "1_1") (pintype "passive"))
      (node (ref "U0") (pin "22") (pinfunction "(MISO/PCINT3)PB3_22") (pintype "passive"))
    )
    (net (code "30") (name "/PWM1") (class "Default")
      (node (ref "P10") (pin "2") (pinfunction "2_2") (pintype "passive"))
      (node (ref "U0") (pin "23") (pinfunction "(OC2A/PCINT4)PB4_23") (pintype "passive"))
    )
    (net (code "31") (name "/PWM2") (class "Default")
      (node (ref "P11") (pin "2") (pinfunction "2_2") (pintype "passive"))
      (node (ref "U0") (pin "24") (pinfunction "(OC1A/PCINT5)PB5_24") (pintype "passive"))
    )
    (net (code "32") (name "/PWM3") (class "Default")
      (node (ref "P12") (pin "2") (pinfunction "2_2") (pintype "passive"))
      (node (ref "U0") (pin "25") (pinfunction "(OC1B/PCINT6)PB6_25") (pintype "passive"))
    )
    (net (code "33") (name "/PWM4") (class "Default")
      (node (ref "P13") (pin "2") (pinfunction "2_2") (pintype "passive"))
      (node (ref "U0") (pin "26") (pinfunction "(OC0A/OC1C/PCINT7)PB7_26") (pintype "passive"))
    )
    (net (code "34") (name "/RESET") (class "Default")
      (node (ref "C3") (pin "2") (pintype "passive"))
      (node (ref "P7") (pin "5") (pinfunction "5_5") (pintype "passive"))
      (node (ref "R2") (pin "1") (pinfunction "1_1") (pintype "passive"))
      (node (ref "S1") (pin "2") (pinfunction "2_2") (pintype "passive"))
      (node (ref "U0") (pin "30") (pinfunction "RESET_30") (pintype "passive"))
    )
    (net (code "35") (name "/RXD0") (class "Default")
      (node (ref "P9") (pin "2") (pinfunction "2_2") (pintype "passive"))
      (node (ref "U0") (pin "3") (pinfunction "(TXD0)PE1_3") (pintype "passive"))
    )
    (net (code "36") (name "/RXD1") (class "Default")
      (node (ref "U0") (pin "45") (pinfunction "(RXD1/INT2)PD2_45") (pintype "passive"))
    )
    (net (code "37") (name "/RXD2") (class "Default")
      (node (ref "U0") (pin "12") (pinfunction "PH0(RXD2)_12") (pintype "passive"))
    )
    (net (code "38") (name "/RXD3") (class "Default")
      (node (ref "U0") (pin "64") (pinfunction "PJ1(TXD3/PCINT10)_64") (pintype "passive"))
    )
    (net (code "39") (name "/SCL") (class "Default")
      (node (ref "P14") (pin "3") (pinfunction "3_3") (pintype "passive"))
      (node (ref "P4") (pin "2") (pinfunction "2_2") (pintype "passive"))
      (node (ref "R10") (pin "2") (pintype "passive"))
      (node (ref "U0") (pin "43") (pinfunction "(SCL/INT0)PD0_43") (pintype "passive"))
    )
    (net (code "40") (name "/SDA") (class "Default")
      (node (ref "P14") (pin "4") (pinfunction "4_4") (pintype "passive"))
      (node (ref "P4") (pin "1") (pinfunction "1_1") (pintype "passive"))
      (node (ref "R9") (pin "2") (pintype "passive"))
      (node (ref "U0") (pin "44") (pinfunction "(SDA/INT1)PD1_44") (pintype "passive"))
    )
    (net (code "41") (name "/TXD0") (class "Default")
      (node (ref "P9") (pin "3") (pinfunction "3_3") (pintype "passive"))
      (node (ref "U0") (pin "2") (pinfunction "(RXD0/PCIN8)PE0_2") (pintype "passive"))
    )
    (net (code "42") (name "/TXD1") (class "Default")
      (node (ref "U0") (pin "46") (pinfunction "(TXD1/INT3)PD3_46") (pintype "passive"))
    )
    (net (code "43") (name "/TXD2") (class "Default")
      (node (ref "U0") (pin "13") (pinfunction "PH1(TXD2)_13") (pintype "passive"))
    )
    (net (code "44") (name "/TXD3") (class "Default")
      (node (ref "U0") (pin "63") (pinfunction "PJ0(RXD3/PCINT9)_63") (pintype "passive"))
    )
    (net (code "45") (name "/V-OUT") (class "Default")
      (node (ref "P8") (pin "5") (pinfunction "5_5") (pintype "passive"))
      (node (ref "U0") (pin "6") (pinfunction "(OC3B/INT4)PE4_6") (pintype "passive"))
    )
    (net (code "46") (name "/Vc0") (class "Default")
      (node (ref "D30") (pin "1") (pinfunction "A_1") (pintype "passive"))
      (node (ref "P2") (pin "16") (pinfunction "16_16") (pintype "passive"))
      (node (ref "R19") (pin "2") (pinfunction "2_2") (pintype "passive"))
    )
    (net (code "47") (name "/Vc1") (class "Default")
      (node (ref "D31") (pin "1") (pinfunction "A_1") (pintype "passive"))
      (node (ref "P2") (pin "14") (pinfunction "14_14") (pintype "passive"))
      (node (ref "R20") (pin "2") (pinfunction "2_2") (pintype "passive"))
    )
    (net (code "48") (name "/Vc2") (class "Default")
      (node (ref "D32") (pin "1") (pinfunction "A_1") (pintype "passive"))
      (node (ref "P2") (pin "12") (pinfunction "12_12") (pintype "passive"))
      (node (ref "R21") (pin "2") (pinfunction "2_2") (pintype "passive"))
    )
    (net (code "49") (name "/Vc3") (class "Default")
      (node (ref "D33") (pin "1") (pinfunction "A_1") (pintype "passive"))
      (node (ref "P2") (pin "10") (pinfunction "10_10") (pintype "passive"))
      (node (ref "R22") (pin "2") (pinfunction "2_2") (pintype "passive"))
    )
    (net (code "50") (name "/Vc4") (class "Default")
      (node (ref "D34") (pin "1") (pinfunction "A_1") (pintype "passive"))
      (node (ref "P2") (pin "8") (pinfunction "8_8") (pintype "passive"))
      (node (ref "R23") (pin "2") (pinfunction "2_2") (pintype "passive"))
    )
    (net (code "51") (name "/Vc5") (class "Default")
      (node (ref "D35") (pin "1") (pinfunction "A_1") (pintype "passive"))
      (node (ref "P2") (pin "6") (pinfunction "6_6") (pintype "passive"))
      (node (ref "R24") (pin "2") (pinfunction "2_2") (pintype "passive"))
    )
    (net (code "52") (name "/Vc6") (class "Default")
      (node (ref "D36") (pin "1") (pinfunction "A_1") (pintype "passive"))
      (node (ref "P2") (pin "4") (pinfunction "4_4") (pintype "passive"))
      (node (ref "R25") (pin "2") (pinfunction "2_2") (pintype "passive"))
    )
    (net (code "53") (name "/Vc7") (class "Default")
      (node (ref "D37") (pin "1") (pinfunction "A_1") (pintype "passive"))
      (node (ref "P2") (pin "2") (pinfunction "2_2") (pintype "passive"))
      (node (ref "R26") (pin "2") (pinfunction "2_2") (pintype "passive"))
    )
    (net (code "54") (name "/Vcell") (class "Default")
      (node (ref "C14") (pin "1") (pinfunction "VCC_1") (pintype "passive"))
      (node (ref "C16") (pin "1") (pinfunction "1_1") (pintype "passive"))
      (node (ref "C17") (pin "1") (pinfunction "1_1") (pintype "passive"))
      (node (ref "C18") (pin "1") (pinfunction "1_1") (pintype "passive"))
      (node (ref "C19") (pin "1") (pinfunction "1_1") (pintype "passive"))
      (node (ref "D0") (pin "2") (pinfunction "K_2") (pintype "passive"))
      (node (ref "D1") (pin "2") (pinfunction "K_2") (pintype "passive"))
      (node (ref "D2") (pin "2") (pinfunction "K_2") (pintype "passive"))
      (node (ref "D3") (pin "2") (pinfunction "K_2") (pintype "passive"))
      (node (ref "D40") (pin "2") (pinfunction "K_2") (pintype "passive"))
      (node (ref "D41") (pin "2") (pinfunction "K_2") (pintype "passive"))
      (node (ref "P1") (pin "20") (pinfunction "20_20") (pintype "passive"))
      (node (ref "U1") (pin "6") (pinfunction "VS_6") (pintype "power_in"))
      (node (ref "U3") (pin "1") (pinfunction "1_1") (pintype "passive"))
      (node (ref "U5") (pin "6") (pinfunction "VS_6") (pintype "power_in"))
    )
    (net (code "55") (name "/Vin") (class "Default")
      (node (ref "C11") (pin "2") (pinfunction "2_2") (pintype "passive"))
      (node (ref "C12") (pin "1") (pinfunction "1_1") (pintype "passive"))
      (node (ref "D30") (pin "2") (pinfunction "K_2") (pintype "passive"))
      (node (ref "D31") (pin "2") (pinfunction "K_2") (pintype "passive"))
      (node (ref "D32") (pin "2") (pinfunction "K_2") (pintype "passive"))
      (node (ref "D33") (pin "2") (pinfunction "K_2") (pintype "passive"))
      (node (ref "D34") (pin "2") (pinfunction "K_2") (pintype "passive"))
      (node (ref "D35") (pin "2") (pinfunction "K_2") (pintype "passive"))
      (node (ref "D36") (pin "2") (pinfunction "K_2") (pintype "passive"))
      (node (ref "D37") (pin "2") (pinfunction "K_2") (pintype "passive"))
      (node (ref "U2") (pin "1") (pinfunction "Vin_1") (pintype "passive"))
    )
    (net (code "56") (name "/Vt") (class "Default")
      (node (ref "D22") (pin "2") (pinfunction "K_2") (pintype "passive"))
      (node (ref "D23") (pin "2") (pinfunction "K_2") (pintype "passive"))
      (node (ref "D24") (pin "2") (pinfunction "K_2") (pintype "passive"))
      (node (ref "D25") (pin "2") (pinfunction "K_2") (pintype "passive"))
      (node (ref "D26") (pin "2") (pinfunction "K_2") (pintype "passive"))
      (node (ref "D27") (pin "2") (pinfunction "K_2") (pintype "passive"))
      (node (ref "D28") (pin "2") (pinfunction "K_2") (pintype "passive"))
      (node (ref "D29") (pin "2") (pinfunction "K_2") (pintype "passive"))
      (node (ref "Rt") (pin "2") (pinfunction "2_2") (pintype "passive"))
    )
    (net (code "57") (name "/Vt0") (class "Default")
      (node (ref "D22") (pin "1") (pinfunction "A_1") (pintype "passive"))
      (node (ref "P6") (pin "15") (pinfunction "15_15") (pintype "passive"))
      (node (ref "R11") (pin "2") (pinfunction "2_2") (pintype "passive"))
    )
    (net (code "58") (name "/Vt1") (class "Default")
      (node (ref "D23") (pin "1") (pinfunction "A_1") (pintype "passive"))
      (node (ref "P6") (pin "13") (pinfunction "13_13") (pintype "passive"))
      (node (ref "R12") (pin "2") (pinfunction "2_2") (pintype "passive"))
    )
    (net (code "59") (name "/Vt2") (class "Default")
      (node (ref "D24") (pin "1") (pinfunction "A_1") (pintype "passive"))
      (node (ref "P6") (pin "11") (pinfunction "11_11") (pintype "passive"))
      (node (ref "R13") (pin "2") (pinfunction "2_2") (pintype "passive"))
    )
    (net (code "60") (name "/Vt3") (class "Default")
      (node (ref "D25") (pin "1") (pinfunction "A_1") (pintype "passive"))
      (node (ref "P6") (pin "9") (pinfunction "9_9") (pintype "passive"))
      (node (ref "R14") (pin "2") (pinfunction "2_2") (pintype "passive"))
    )
    (net (code "61") (name "/Vt4") (class "Default")
      (node (ref "D26") (pin "1") (pinfunction "A_1") (pintype "passive"))
      (node (ref "P6") (pin "7") (pinfunction "7_7") (pintype "passive"))
      (node (ref "R15") (pin "2") (pinfunction "2_2") (pintype "passive"))
    )
    (net (code "62") (name "/Vt5") (class "Default")
      (node (ref "D27") (pin "1") (pinfunction "A_1") (pintype "passive"))
      (node (ref "P6") (pin "5") (pinfunction "5_5") (pintype "passive"))
      (node (ref "R16") (pin "2") (pinfunction "2_2") (pintype "passive"))
    )
    (net (code "63") (name "/Vt6") (class "Default")
      (node (ref "D28") (pin "1") (pinfunction "A_1") (pintype "passive"))
      (node (ref "P6") (pin "3") (pinfunction "3_3") (pintype "passive"))
      (node (ref "R17") (pin "2") (pinfunction "2_2") (pintype "passive"))
    )
    (net (code "64") (name "/Vt7") (class "Default")
      (node (ref "D29") (pin "1") (pinfunction "A_1") (pintype "passive"))
      (node (ref "P6") (pin "1") (pinfunction "1_1") (pintype "passive"))
      (node (ref "R18") (pin "2") (pinfunction "2_2") (pintype "passive"))
    )
    (net (code "65") (name "/XTAL1") (class "Default")
      (node (ref "C2") (pin "2") (pintype "passive"))
      (node (ref "R1") (pin "1") (pinfunction "1_1") (pintype "passive"))
      (node (ref "U0") (pin "34") (pinfunction "XTAL1_34") (pintype "passive"))
      (node (ref "Y1") (pin "1") (pinfunction "OSC1_1") (pintype "passive"))
    )
    (net (code "66") (name "/XTAL2") (class "Default")
      (node (ref "C1") (pin "2") (pintype "passive"))
      (node (ref "R1") (pin "2") (pinfunction "2_2") (pintype "passive"))
      (node (ref "U0") (pin "33") (pinfunction "XTAL2_33") (pintype "output"))
      (node (ref "Y1") (pin "2") (pinfunction "OSC2_2") (pintype "passive"))
    )
    (net (code "67") (name "/motor1") (class "Default")
      (node (ref "D40") (pin "1") (pinfunction "A_1") (pintype "passive"))
      (node (ref "D42") (pin "2") (pinfunction "K_2") (pintype "passive"))
      (node (ref "P8") (pin "10") (pinfunction "10_10") (pintype "passive"))
      (node (ref "U5") (pin "4") (pinfunction "OUT1_4") (pintype "output"))
    )
    (net (code "68") (name "/motor2") (class "Default")
      (node (ref "D41") (pin "1") (pinfunction "A_1") (pintype "passive"))
      (node (ref "D43") (pin "2") (pinfunction "K_2") (pintype "passive"))
      (node (ref "P8") (pin "12") (pinfunction "12_12") (pintype "passive"))
      (node (ref "U5") (pin "5") (pinfunction "OUT2_5") (pintype "output"))
    )
    (net (code "69") (name "AGND") (class "Default")
      (node (ref "C1") (pin "1") (pintype "passive"))
      (node (ref "C10") (pin "2") (pinfunction "2_2") (pintype "passive"))
      (node (ref "C11") (pin "1") (pinfunction "1_1") (pintype "passive"))
      (node (ref "C12") (pin "2") (pinfunction "2_2") (pintype "passive"))
      (node (ref "C13") (pin "2") (pinfunction "GND_2") (pintype "passive"))
      (node (ref "C14") (pin "2") (pinfunction "GND_2") (pintype "passive"))
      (node (ref "C15") (pin "2") (pinfunction "2_2") (pintype "passive"))
      (node (ref "C16") (pin "2") (pinfunction "2_2") (pintype "passive"))
      (node (ref "C17") (pin "2") (pinfunction "2_2") (pintype "passive"))
      (node (ref "C18") (pin "2") (pinfunction "2_2") (pintype "passive"))
      (node (ref "C19") (pin "2") (pinfunction "2_2") (pintype "passive"))
      (node (ref "C2") (pin "1") (pintype "passive"))
      (node (ref "C20") (pin "2") (pinfunction "2_2") (pintype "passive"))
      (node (ref "C3") (pin "1") (pintype "passive"))
      (node (ref "C4") (pin "1") (pintype "passive"))
      (node (ref "C5") (pin "1") (pintype "passive"))
      (node (ref "C6") (pin "1") (pintype "passive"))
      (node (ref "C7") (pin "1") (pintype "passive"))
      (node (ref "C8") (pin "1") (pintype "passive"))
      (node (ref "C9") (pin "1") (pinfunction "1_1") (pintype "passive"))
      (node (ref "D10") (pin "2") (pinfunction "K_2") (pintype "passive"))
      (node (ref "D11") (pin "2") (pinfunction "K_2") (pintype "passive"))
      (node (ref "D12") (pin "2") (pinfunction "K_2") (pintype "passive"))
      (node (ref "D13") (pin "2") (pinfunction "K_2") (pintype "passive"))
      (node (ref "D14") (pin "2") (pinfunction "K_2") (pintype "passive"))
      (node (ref "D15") (pin "2") (pinfunction "K_2") (pintype "passive"))
      (node (ref "D16") (pin "2") (pinfunction "K_2") (pintype "passive"))
      (node (ref "D17") (pin "2") (pinfunction "K_2") (pintype "passive"))
      (node (ref "D18") (pin "2") (pinfunction "K_2") (pintype "passive"))
      (node (ref "D19") (pin "2") (pinfunction "K_2") (pintype "passive"))
      (node (ref "D20") (pin "2") (pinfunction "K_2") (pintype "passive"))
      (node (ref "D21") (pin "2") (pinfunction "K_2") (pintype "passive"))
      (node (ref "D38") (pin "1") (pinfunction "A_1") (pintype "passive"))
      (node (ref "D39") (pin "1") (pinfunction "A_1") (pintype "passive"))
      (node (ref "D4") (pin "1") (pinfunction "A_1") (pintype "passive"))
      (node (ref "D42") (pin "1") (pinfunction "A_1") (pintype "passive"))
      (node (ref "D43") (pin "1") (pinfunction "A_1") (pintype "passive"))
      (node (ref "D44") (pin "2") (pinfunction "2_2") (pintype "passive"))
      (node (ref "D5") (pin "1") (pinfunction "A_1") (pintype "passive"))
      (node (ref "D6") (pin "2") (pinfunction "K_2") (pintype "passive"))
      (node (ref "D7") (pin "2") (pinfunction "K_2") (pintype "passive"))
      (node (ref "D8") (pin "2") (pinfunction "K_2") (pintype "passive"))
      (node (ref "D9") (pin "2") (pinfunction "K_2") (pintype "passive"))
      (node (ref "L31") (pin "1") (pinfunction "1_1") (pintype "passive"))
      (node (ref "P1") (pin "1") (pinfunction "1_1") (pintype "passive"))
      (node (ref "P1") (pin "11") (pinfunction "11_11") (pintype "passive"))
      (node (ref "P1") (pin "13") (pinfunction "13_13") (pintype "passive"))
      (node (ref "P1") (pin "15") (pinfunction "15_15") (pintype "passive"))
      (node (ref "P1") (pin "17") (pinfunction "17_17") (pintype "passive"))
      (node (ref "P1") (pin "19") (pinfunction "19_19") (pintype "passive"))
      (node (ref "P1") (pin "3") (pinfunction "3_3") (pintype "passive"))
      (node (ref "P1") (pin "5") (pinfunction "5_5") (pintype "passive"))
      (node (ref "P1") (pin "7") (pinfunction "7_7") (pintype "passive"))
      (node (ref "P1") (pin "9") (pinfunction "9_9") (pintype "passive"))
      (node (ref "P10") (pin "3") (pinfunction "3_3") (pintype "passive"))
      (node (ref "P11") (pin "3") (pinfunction "3_3") (pintype "passive"))
      (node (ref "P12") (pin "3") (pinfunction "3_3") (pintype "passive"))
      (node (ref "P13") (pin "3") (pinfunction "3_3") (pintype "passive"))
      (node (ref "P14") (pin "2") (pinfunction "2_2") (pintype "passive"))
      (node (ref "P4") (pin "4") (pinfunction "4_4") (pintype "passive"))
      (node (ref "P5") (pin "10") (pinfunction "10_10") (pintype "passive"))
      (node (ref "P5") (pin "12") (pinfunction "12_12") (pintype "passive"))
      (node (ref "P5") (pin "14") (pinfunction "14_14") (pintype "passive"))
      (node (ref "P5") (pin "16") (pinfunction "16_16") (pintype "passive"))
      (node (ref "P5") (pin "18") (pinfunction "18_18") (pintype "passive"))
      (node (ref "P5") (pin "2") (pinfunction "2_2") (pintype "passive"))
      (node (ref "P5") (pin "4") (pinfunction "4_4") (pintype "passive"))
      (node (ref "P5") (pin "6") (pinfunction "6_6") (pintype "passive"))
      (node (ref "P5") (pin "8") (pinfunction "8_8") (pintype "passive"))
      (node (ref "P7") (pin "6") (pinfunction "6_6") (pintype "passive"))
      (node (ref "P8") (pin "11") (pinfunction "11_11") (pintype "passive"))
      (node (ref "P8") (pin "7") (pinfunction "7_7") (pintype "passive"))
      (node (ref "P8") (pin "9") (pinfunction "9_9") (pintype "passive"))
      (node (ref "P9") (pin "4") (pinfunction "4_4") (pintype "passive"))
      (node (ref "R6") (pin "2") (pinfunction "2_2") (pintype "passive"))
      (node (ref "Rt") (pin "1") (pinfunction "1_1") (pintype "passive"))
      (node (ref "S1") (pin "1") (pinfunction "1_1") (pintype "passive"))
      (node (ref "U0") (pin "11") (pinfunction "GND_11") (pintype "power_in"))
      (node (ref "U0") (pin "32") (pinfunction "GND1_32") (pintype "power_in"))
      (node (ref "U0") (pin "62") (pinfunction "GND2_62") (pintype "power_in"))
      (node (ref "U0") (pin "81") (pinfunction "GND3_81") (pintype "power_in"))
      (node (ref "U0") (pin "99") (pinfunction "AGND_99") (pintype "power_in"))
      (node (ref "U1") (pin "1") (pinfunction "GND_1") (pintype "power_in"))
      (node (ref "U1") (pin "10") (pinfunction "GND_10") (pintype "power_in"))
      (node (ref "U1") (pin "11") (pinfunction "GND_11") (pintype "power_in"))
      (node (ref "U1") (pin "19") (pinfunction "ISEN_B_19") (pintype "passive"))
      (node (ref "U1") (pin "2") (pinfunction "ISEN_A_2") (pintype "passive"))
      (node (ref "U1") (pin "20") (pinfunction "GND_20") (pintype "power_in"))
      (node (ref "U2") (pin "2") (pinfunction "GND_2") (pintype "passive"))
      (node (ref "U3") (pin "3") (pinfunction "3_3") (pintype "passive"))
      (node (ref "U3") (pin "5") (pinfunction "5_5") (pintype "passive"))
      (node (ref "U4") (pin "1") (pinfunction "GND_1") (pintype "passive"))
      (node (ref "U5") (pin "1") (pinfunction "GND_1") (pintype "power_in"))
      (node (ref "U5") (pin "10") (pinfunction "GND_10") (pintype "power_in"))
      (node (ref "U5") (pin "11") (pinfunction "GND_11") (pintype "power_in"))
      (node (ref "U5") (pin "19") (pinfunction "ISEN_B_19") (pintype "passive"))
      (node (ref "U5") (pin "2") (pinfunction "ISEN_A_2") (pintype "passive"))
      (node (ref "U5") (pin "20") (pinfunction "GND_20") (pintype "power_in"))
    )
    (net (code "70") (name "Net-(C21-Pad1)") (class "Default")
      (node (ref "C21") (pin "1") (pinfunction "1_1") (pintype "passive"))
      (node (ref "R6") (pin "1") (pinfunction "1_1") (pintype "passive"))
      (node (ref "R7") (pin "2") (pinfunction "2_2") (pintype "passive"))
      (node (ref "U3") (pin "4") (pinfunction "4_4") (pintype "passive"))
    )
    (net (code "71") (name "Net-(D6-A)") (class "Default")
      (node (ref "D6") (pin "1") (pinfunction "A_1") (pintype "passive"))
      (node (ref "R19") (pin "1") (pinfunction "1_1") (pintype "passive"))
    )
    (net (code "72") (name "Net-(D7-A)") (class "Default")
      (node (ref "D7") (pin "1") (pinfunction "A_1") (pintype "passive"))
      (node (ref "R20") (pin "1") (pinfunction "1_1") (pintype "passive"))
    )
    (net (code "73") (name "Net-(D8-A)") (class "Default")
      (node (ref "D8") (pin "1") (pinfunction "A_1") (pintype "passive"))
      (node (ref "R21") (pin "1") (pinfunction "1_1") (pintype "passive"))
    )
    (net (code "74") (name "Net-(D9-A)") (class "Default")
      (node (ref "D9") (pin "1") (pinfunction "A_1") (pintype "passive"))
      (node (ref "R22") (pin "1") (pinfunction "1_1") (pintype "passive"))
    )
    (net (code "75") (name "Net-(D10-A)") (class "Default")
      (node (ref "D10") (pin "1") (pinfunction "A_1") (pintype "passive"))
      (node (ref "R23") (pin "1") (pinfunction "1_1") (pintype "passive"))
    )
    (net (code "76") (name "Net-(D11-A)") (class "Default")
      (node (ref "D11") (pin "1") (pinfunction "A_1") (pintype "passive"))
      (node (ref "R24") (pin "1") (pinfunction "1_1") (pintype "passive"))
    )
    (net (code "77") (name "Net-(D12-A)") (class "Default")
      (node (ref "D12") (pin "1") (pinfunction "A_1") (pintype "passive"))
      (node (ref "R25") (pin "1") (pinfunction "1_1") (pintype "passive"))
    )
    (net (code "78") (name "Net-(D13-A)") (class "Default")
      (node (ref "D13") (pin "1") (pinfunction "A_1") (pintype "passive"))
      (node (ref "R26") (pin "1") (pinfunction "1_1") (pintype "passive"))
    )
    (net (code "79") (name "Net-(D14-A)") (class "Default")
      (node (ref "D14") (pin "1") (pinfunction "A_1") (pintype "passive"))
      (node (ref "R11") (pin "1") (pinfunction "1_1") (pintype "passive"))
    )
    (net (code "80") (name "Net-(D15-A)") (class "Default")
      (node (ref "D15") (pin "1") (pinfunction "A_1") (pintype "passive"))
      (node (ref "R12") (pin "1") (pinfunction "1_1") (pintype "passive"))
    )
    (net (code "81") (name "Net-(D16-A)") (class "Default")
      (node (ref "D16") (pin "1") (pinfunction "A_1") (pintype "passive"))
      (node (ref "R13") (pin "1") (pinfunction "1_1") (pintype "passive"))
    )
    (net (code "82") (name "Net-(D17-A)") (class "Default")
      (node (ref "D17") (pin "1") (pinfunction "A_1") (pintype "passive"))
      (node (ref "R14") (pin "1") (pinfunction "1_1") (pintype "passive"))
    )
    (net (code "83") (name "Net-(D18-A)") (class "Default")
      (node (ref "D18") (pin "1") (pinfunction "A_1") (pintype "passive"))
      (node (ref "R15") (pin "1") (pinfunction "1_1") (pintype "passive"))
    )
    (net (code "84") (name "Net-(D19-A)") (class "Default")
      (node (ref "D19") (pin "1") (pinfunction "A_1") (pintype "passive"))
      (node (ref "R16") (pin "1") (pinfunction "1_1") (pintype "passive"))
    )
    (net (code "85") (name "Net-(D20-A)") (class "Default")
      (node (ref "D20") (pin "1") (pinfunction "A_1") (pintype "passive"))
      (node (ref "R17") (pin "1") (pinfunction "1_1") (pintype "passive"))
    )
    (net (code "86") (name "Net-(D21-A)") (class "Default")
      (node (ref "D21") (pin "1") (pinfunction "A_1") (pintype "passive"))
      (node (ref "R18") (pin "1") (pinfunction "1_1") (pintype "passive"))
    )
    (net (code "87") (name "Net-(D44-Pad1)") (class "Default")
      (node (ref "D44") (pin "1") (pinfunction "1_1") (pintype "passive"))
      (node (ref "R5") (pin "2") (pinfunction "2_2") (pintype "passive"))
    )
    (net (code "88") (name "Net-(L2-Pad1)") (class "Default")
      (node (ref "L2") (pin "1") (pinfunction "1_1") (pintype "passive"))
      (node (ref "L31") (pin "2") (pinfunction "2_2") (pintype "passive"))
      (node (ref "U3") (pin "2") (pinfunction "2_2") (pintype "passive"))
    )
    (net (code "89") (name "Net-(P1-Pad2)") (class "Default")
      (node (ref "P1") (pin "2") (pinfunction "2_2") (pintype "passive"))
      (node (ref "P2") (pin "1") (pinfunction "1_1") (pintype "passive"))
    )
    (net (code "90") (name "Net-(P1-Pad4)") (class "Default")
      (node (ref "P1") (pin "4") (pinfunction "4_4") (pintype "passive"))
      (node (ref "P2") (pin "3") (pinfunction "3_3") (pintype "passive"))
    )
    (net (code "91") (name "Net-(P1-Pad6)") (class "Default")
      (node (ref "P1") (pin "6") (pinfunction "6_6") (pintype "passive"))
      (node (ref "P2") (pin "5") (pinfunction "5_5") (pintype "passive"))
    )
    (net (code "92") (name "Net-(P1-Pad8)") (class "Default")
      (node (ref "P1") (pin "8") (pinfunction "8_8") (pintype "passive"))
      (node (ref "P2") (pin "7") (pinfunction "7_7") (pintype "passive"))
    )
    (net (code "93") (name "Net-(P1-Pad10)") (class "Default")
      (node (ref "P1") (pin "10") (pinfunction "10_10") (pintype "passive"))
      (node (ref "P2") (pin "9") (pinfunction "9_9") (pintype "passive"))
    )
    (net (code "94") (name "Net-(P1-Pad12)") (class "Default")
      (node (ref "P1") (pin "12") (pinfunction "12_12") (pintype "passive"))
      (node (ref "P2") (pin "11") (pinfunction "11_11") (pintype "passive"))
    )
    (net (code "95") (name "Net-(P1-Pad14)") (class "Default")
      (node (ref "P1") (pin "14") (pinfunction "14_14") (pintype "passive"))
      (node (ref "P2") (pin "13") (pinfunction "13_13") (pintype "passive"))
    )
    (net (code "96") (name "Net-(P1-Pad16)") (class "Default")
      (node (ref "P1") (pin "16") (pinfunction "16_16") (pintype "passive"))
      (node (ref "P2") (pin "15") (pinfunction "15_15") (pintype "passive"))
    )
    (net (code "97") (name "Net-(P3-Pad2)") (class "Default")
      (node (ref "P3") (pin "2") (pinfunction "2_2") (pintype "passive"))
      (node (ref "P4") (pin "5") (pinfunction "5_5") (pintype "passive"))
    )
    (net (code "98") (name "Net-(P3-Pad4)") (class "Default")
      (node (ref "P3") (pin "4") (pinfunction "4_4") (pintype "passive"))
      (node (ref "P4") (pin "7") (pinfunction "7_7") (pintype "passive"))
    )
    (net (code "99") (name "Net-(P3-Pad6)") (class "Default")
      (node (ref "P3") (pin "6") (pinfunction "6_6") (pintype "passive"))
      (node (ref "P4") (pin "9") (pinfunction "9_9") (pintype "passive"))
    )
    (net (code "100") (name "Net-(P3-Pad8)") (class "Default")
      (node (ref "P3") (pin "8") (pinfunction "8_8") (pintype "passive"))
      (node (ref "P4") (pin "11") (pinfunction "11_11") (pintype "passive"))
    )
    (net (code "101") (name "Net-(P3-Pad10)") (class "Default")
      (node (ref "P3") (pin "10") (pinfunction "10_10") (pintype "passive"))
      (node (ref "P4") (pin "13") (pinfunction "13_13") (pintype "passive"))
    )
    (net (code "102") (name "Net-(P3-Pad12)") (class "Default")
      (node (ref "P3") (pin "12") (pinfunction "12_12") (pintype "passive"))
      (node (ref "P4") (pin "15") (pinfunction "15_15") (pintype "passive"))
    )
    (net (code "103") (name "Net-(P3-Pad14)") (class "Default")
      (node (ref "P3") (pin "14") (pinfunction "14_14") (pintype "passive"))
      (node (ref "P4") (pin "17") (pinfunction "17_17") (pintype "passive"))
    )
    (net (code "104") (name "Net-(P3-Pad16)") (class "Default")
      (node (ref "P3") (pin "16") (pinfunction "16_16") (pintype "passive"))
      (node (ref "P4") (pin "19") (pinfunction "19_19") (pintype "passive"))
    )
    (net (code "105") (name "Net-(P5-Pad1)") (class "Default")
      (node (ref "P5") (pin "1") (pinfunction "1_1") (pintype "passive"))
      (node (ref "P6") (pin "2") (pinfunction "2_2") (pintype "passive"))
    )
    (net (code "106") (name "Net-(P5-Pad3)") (class "Default")
      (node (ref "P5") (pin "3") (pinfunction "3_3") (pintype "passive"))
      (node (ref "P6") (pin "4") (pinfunction "4_4") (pintype "passive"))
    )
    (net (code "107") (name "Net-(P5-Pad5)") (class "Default")
      (node (ref "P5") (pin "5") (pinfunction "5_5") (pintype "passive"))
      (node (ref "P6") (pin "6") (pinfunction "6_6") (pintype "passive"))
    )
    (net (code "108") (name "Net-(P5-Pad7)") (class "Default")
      (node (ref "P5") (pin "7") (pinfunction "7_7") (pintype "passive"))
      (node (ref "P6") (pin "8") (pinfunction "8_8") (pintype "passive"))
    )
    (net (code "109") (name "Net-(P5-Pad9)") (class "Default")
      (node (ref "P5") (pin "9") (pinfunction "9_9") (pintype "passive"))
      (node (ref "P6") (pin "10") (pinfunction "10_10") (pintype "passive"))
    )
    (net (code "110") (name "Net-(P5-Pad11)") (class "Default")
      (node (ref "P5") (pin "11") (pinfunction "11_11") (pintype "passive"))
      (node (ref "P6") (pin "12") (pinfunction "12_12") (pintype "passive"))
    )
    (net (code "111") (name "Net-(P5-Pad13)") (class "Default")
      (node (ref "P5") (pin "13") (pinfunction "13_13") (pintype "passive"))
      (node (ref "P6") (pin "14") (pinfunction "14_14") (pintype "passive"))
    )
    (net (code "112") (name "Net-(P5-Pad15)") (class "Default")
      (node (ref "P5") (pin "15") (pinfunction "15_15") (pintype "passive"))
      (node (ref "P6") (pin "16") (pinfunction "16_16") (pintype "passive"))
    )
    (net (code "113") (name "PWMV") (class "Default")
      (node (ref "C13") (pin "1") (pinfunction "VCC_1") (pintype "passive"))
      (node (ref "C21") (pin "2") (pinfunction "2_2") (pintype "passive"))
      (node (ref "L2") (pin "2") (pinfunction "2_2") (pintype "passive"))
      (node (ref "P10") (pin "1") (pinfunction "1_1") (pintype "passive"))
      (node (ref "P11") (pin "1") (pinfunction "1_1") (pintype "passive"))
      (node (ref "P12") (pin "1") (pinfunction "1_1") (pintype "passive"))
      (node (ref "P13") (pin "1") (pinfunction "1_1") (pintype "passive"))
      (node (ref "R7") (pin "1") (pinfunction "1_1") (pintype "passive"))
    )
    (net (code "114") (name "unconnected-(P1-Pad18)") (class "Default")
      (node (ref "P1") (pin "18") (pinfunction "18_18") (pintype "passive"))
    )
    (net (code "115") (name "unconnected-(P4-Pad6)") (class "Default")
      (node (ref "P4") (pin "6") (pinfunction "6_6") (pintype "passive"))
    )
    (net (code "116") (name "unconnected-(P4-Pad8)") (class "Default")
      (node (ref "P4") (pin "8") (pinfunction "8_8") (pintype "passive"))
    )
    (net (code "117") (name "unconnected-(P4-Pad10)") (class "Default")
      (node (ref "P4") (pin "10") (pinfunction "10_10") (pintype "passive"))
    )
    (net (code "118") (name "unconnected-(P4-Pad12)") (class "Default")
      (node (ref "P4") (pin "12") (pinfunction "12_12") (pintype "passive"))
    )
    (net (code "119") (name "unconnected-(P4-Pad14)") (class "Default")
      (node (ref "P4") (pin "14") (pinfunction "14_14") (pintype "passive"))
    )
    (net (code "120") (name "unconnected-(P4-Pad16)") (class "Default")
      (node (ref "P4") (pin "16") (pinfunction "16_16") (pintype "passive"))
    )
    (net (code "121") (name "unconnected-(P4-Pad18)") (class "Default")
      (node (ref "P4") (pin "18") (pinfunction "18_18") (pintype "passive"))
    )
    (net (code "122") (name "unconnected-(P4-Pad20)") (class "Default")
      (node (ref "P4") (pin "20") (pinfunction "20_20") (pintype "passive"))
    )
    (net (code "123") (name "unconnected-(P5-Pad17)") (class "Default")
      (node (ref "P5") (pin "17") (pinfunction "17_17") (pintype "passive"))
    )
    (net (code "124") (name "unconnected-(P5-Pad19)") (class "Default")
      (node (ref "P5") (pin "19") (pinfunction "19_19") (pintype "passive"))
    )
    (net (code "125") (name "unconnected-(P5-Pad20)") (class "Default")
      (node (ref "P5") (pin "20") (pinfunction "20_20") (pintype "passive"))
    )
    (net (code "126") (name "unconnected-(U0-(AD0)PA0-Pad78)") (class "Default")
      (node (ref "U0") (pin "78") (pinfunction "(AD0)PA0_78") (pintype "passive"))
    )
    (net (code "127") (name "unconnected-(U0-(AD1)PA1-Pad77)") (class "Default")
      (node (ref "U0") (pin "77") (pinfunction "(AD1)PA1_77") (pintype "passive"))
    )
    (net (code "128") (name "unconnected-(U0-(AD2)PA2-Pad76)") (class "Default")
      (node (ref "U0") (pin "76") (pinfunction "(AD2)PA2_76") (pintype "passive"))
    )
    (net (code "129") (name "unconnected-(U0-(AD3)PA3-Pad75)") (class "Default")
      (node (ref "U0") (pin "75") (pinfunction "(AD3)PA3_75") (pintype "passive"))
    )
    (net (code "130") (name "unconnected-(U0-(AD4)PA4-Pad74)") (class "Default")
      (node (ref "U0") (pin "74") (pinfunction "(AD4)PA4_74") (pintype "passive"))
    )
    (net (code "131") (name "unconnected-(U0-(AD5)PA5-Pad73)") (class "Default")
      (node (ref "U0") (pin "73") (pinfunction "(AD5)PA5_73") (pintype "passive"))
    )
    (net (code "132") (name "unconnected-(U0-(AD6)PA6-Pad72)") (class "Default")
      (node (ref "U0") (pin "72") (pinfunction "(AD6)PA6_72") (pintype "passive"))
    )
    (net (code "133") (name "unconnected-(U0-(AD7)PA7-Pad71)") (class "Default")
      (node (ref "U0") (pin "71") (pinfunction "(AD7)PA7_71") (pintype "passive"))
    )
    (net (code "134") (name "unconnected-(U0-(ADC0)PF0-Pad97)") (class "Default")
      (node (ref "U0") (pin "97") (pinfunction "(ADC0)PF0_97") (pintype "passive"))
    )
    (net (code "135") (name "unconnected-(U0-(ADC1)PF1-Pad96)") (class "Default")
      (node (ref "U0") (pin "96") (pinfunction "(ADC1)PF1_96") (pintype "passive"))
    )
    (net (code "136") (name "unconnected-(U0-(ADC2)PF2-Pad95)") (class "Default")
      (node (ref "U0") (pin "95") (pinfunction "(ADC2)PF2_95") (pintype "passive"))
    )
    (net (code "137") (name "unconnected-(U0-(ADC3)PF3-Pad94)") (class "Default")
      (node (ref "U0") (pin "94") (pinfunction "(ADC3)PF3_94") (pintype "passive"))
    )
    (net (code "138") (name "unconnected-(U0-(ADC4{slash}TCK)PF4-Pad93)") (class "Default")
      (node (ref "U0") (pin "93") (pinfunction "(ADC4/TCK)PF4_93") (pintype "passive"))
    )
    (net (code "139") (name "unconnected-(U0-(ADC5{slash}TMS)PF5-Pad92)") (class "Default")
      (node (ref "U0") (pin "92") (pinfunction "(ADC5/TMS)PF5_92") (pintype "passive"))
    )
    (net (code "140") (name "unconnected-(U0-(ADC6{slash}TDO)PF6-Pad91)") (class "Default")
      (node (ref "U0") (pin "91") (pinfunction "(ADC6/TDO)PF6_91") (pintype "passive"))
    )
    (net (code "141") (name "unconnected-(U0-(ADC7{slash}TDI)PF7-Pad90)") (class "Default")
      (node (ref "U0") (pin "90") (pinfunction "(ADC7/TDI)PF7_90") (pintype "passive"))
    )
    (net (code "142") (name "unconnected-(U0-(ALE)PG2-Pad70)") (class "Default")
      (node (ref "U0") (pin "70") (pinfunction "(ALE)PG2_70") (pintype "passive"))
    )
    (net (code "143") (name "unconnected-(U0-(CLKO{slash}ICP3{slash}INT7)PE7-Pad9)") (class "Default")
      (node (ref "U0") (pin "9") (pinfunction "(CLKO/ICP3/INT7)PE7_9") (pintype "passive"))
    )
    (net (code "144") (name "unconnected-(U0-(ICP1)PD4-Pad47)") (class "Default")
      (node (ref "U0") (pin "47") (pinfunction "(ICP1)PD4_47") (pintype "passive"))
    )
    (net (code "145") (name "unconnected-(U0-(OC0B)PG5-Pad1)") (class "Default")
      (node (ref "U0") (pin "1") (pinfunction "(OC0B)PG5_1") (pintype "passive"))
    )
    (net (code "146") (name "unconnected-(U0-(OC3C{slash}INT5)PE5-Pad7)") (class "Default")
      (node (ref "U0") (pin "7") (pinfunction "(OC3C/INT5)PE5_7") (pintype "passive"))
    )
    (net (code "147") (name "unconnected-(U0-(RD)PG1-Pad52)") (class "Default")
      (node (ref "U0") (pin "52") (pinfunction "(RD)PG1_52") (pintype "passive"))
    )
    (net (code "148") (name "unconnected-(U0-(SS{slash}PCINT0)PB0-Pad19)") (class "Default")
      (node (ref "U0") (pin "19") (pinfunction "(SS/PCINT0)PB0_19") (pintype "passive"))
    )
    (net (code "149") (name "unconnected-(U0-(T0)PD7-Pad50)") (class "Default")
      (node (ref "U0") (pin "50") (pinfunction "(T0)PD7_50") (pintype "passive"))
    )
    (net (code "150") (name "unconnected-(U0-(T1)PD6-Pad49)") (class "Default")
      (node (ref "U0") (pin "49") (pinfunction "(T1)PD6_49") (pintype "passive"))
    )
    (net (code "151") (name "unconnected-(U0-(T3{slash}INT6)PE6-Pad8)") (class "Default")
      (node (ref "U0") (pin "8") (pinfunction "(T3/INT6)PE6_8") (pintype "passive"))
    )
    (net (code "152") (name "unconnected-(U0-(TOSC1)PG4-Pad29)") (class "Default")
      (node (ref "U0") (pin "29") (pinfunction "(TOSC1)PG4_29") (pintype "passive"))
    )
    (net (code "153") (name "unconnected-(U0-(TOSC2)PG3-Pad28)") (class "Default")
      (node (ref "U0") (pin "28") (pinfunction "(TOSC2)PG3_28") (pintype "passive"))
    )
    (net (code "154") (name "unconnected-(U0-(WR)PG0-Pad51)") (class "Default")
      (node (ref "U0") (pin "51") (pinfunction "(WR)PG0_51") (pintype "passive"))
    )
    (net (code "155") (name "unconnected-(U0-(XCK0{slash}AIN0)PE2-Pad4)") (class "Default")
      (node (ref "U0") (pin "4") (pinfunction "(XCK0/AIN0)PE2_4") (pintype "passive"))
    )
    (net (code "156") (name "unconnected-(U0-(XCK1)PD5-Pad48)") (class "Default")
      (node (ref "U0") (pin "48") (pinfunction "(XCK1)PD5_48") (pintype "passive"))
    )
    (net (code "157") (name "unconnected-(U0-PH2(XCK2)-Pad14)") (class "Default")
      (node (ref "U0") (pin "14") (pinfunction "PH2(XCK2)_14") (pintype "passive"))
    )
    (net (code "158") (name "unconnected-(U0-PH3(OC4A)-Pad15)") (class "Default")
      (node (ref "U0") (pin "15") (pinfunction "PH3(OC4A)_15") (pintype "passive"))
    )
    (net (code "159") (name "unconnected-(U0-PH4(OC4B)-Pad16)") (class "Default")
      (node (ref "U0") (pin "16") (pinfunction "PH4(OC4B)_16") (pintype "passive"))
    )
    (net (code "160") (name "unconnected-(U0-PH5(OC4C)-Pad17)") (class "Default")
      (node (ref "U0") (pin "17") (pinfunction "PH5(OC4C)_17") (pintype "passive"))
    )
    (net (code "161") (name "unconnected-(U0-PH6(OC2B)-Pad18)") (class "Default")
      (node (ref "U0") (pin "18") (pinfunction "PH6(OC2B)_18") (pintype "passive"))
    )
    (net (code "162") (name "unconnected-(U0-PH7(T4)-Pad27)") (class "Default")
      (node (ref "U0") (pin "27") (pinfunction "PH7(T4)_27") (pintype "passive"))
    )
    (net (code "163") (name "unconnected-(U0-PJ2(XCK3{slash}PCINT11)-Pad65)") (class "Default")
      (node (ref "U0") (pin "65") (pinfunction "PJ2(XCK3/PCINT11)_65") (pintype "passive"))
    )
    (net (code "164") (name "unconnected-(U0-PJ3(PCINT12)-Pad66)") (class "Default")
      (node (ref "U0") (pin "66") (pinfunction "PJ3(PCINT12)_66") (pintype "passive"))
    )
    (net (code "165") (name "unconnected-(U0-PJ4(PCINT13)-Pad67)") (class "Default")
      (node (ref "U0") (pin "67") (pinfunction "PJ4(PCINT13)_67") (pintype "passive"))
    )
    (net (code "166") (name "unconnected-(U0-PJ5(PCINT14)-Pad68)") (class "Default")
      (node (ref "U0") (pin "68") (pinfunction "PJ5(PCINT14)_68") (pintype "passive"))
    )
    (net (code "167") (name "unconnected-(U0-PJ6(PCINT15)-Pad69)") (class "Default")
      (node (ref "U0") (pin "69") (pinfunction "PJ6(PCINT15)_69") (pintype "passive"))
    )
    (net (code "168") (name "unconnected-(U0-PJ7-Pad79)") (class "Default")
      (node (ref "U0") (pin "79") (pinfunction "PJ7_79") (pintype "passive"))
    )
    (net (code "169") (name "unconnected-(U0-PK0(ADC8{slash}PCINT16)-Pad89)") (class "Default")
      (node (ref "U0") (pin "89") (pinfunction "PK0(ADC8/PCINT16)_89") (pintype "passive"))
    )
    (net (code "170") (name "unconnected-(U0-PK1(ADC9{slash}PCINT17)-Pad88)") (class "Default")
      (node (ref "U0") (pin "88") (pinfunction "PK1(ADC9/PCINT17)_88") (pintype "passive"))
    )
    (net (code "171") (name "unconnected-(U0-PK2(ADC10{slash}PCINT18)-Pad87)") (class "Default")
      (node (ref "U0") (pin "87") (pinfunction "PK2(ADC10/PCINT18)_87") (pintype "passive"))
    )
    (net (code "172") (name "unconnected-(U0-PL1(ICP5)-Pad36)") (class "Default")
      (node (ref "U0") (pin "36") (pinfunction "PL1(ICP5)_36") (pintype "passive"))
    )
    (net (code "173") (name "unconnected-(U0-PL2(T5)-Pad37)") (class "Default")
      (node (ref "U0") (pin "37") (pinfunction "PL2(T5)_37") (pintype "passive"))
    )
    (net (code "174") (name "unconnected-(U0-PL5(OC5C)-Pad40)") (class "Default")
      (node (ref "U0") (pin "40") (pinfunction "PL5(OC5C)_40") (pintype "passive"))
    )
    (net (code "175") (name "unconnected-(U0-PL6-Pad41)") (class "Default")
      (node (ref "U0") (pin "41") (pinfunction "PL6_41") (pintype "passive"))
    )
    (net (code "176") (name "unconnected-(U0-PL7-Pad42)") (class "Default")
      (node (ref "U0") (pin "42") (pinfunction "PL7_42") (pintype "passive"))
    )
    (net (code "177") (name "unconnected-(U1-NC-Pad3)") (class "Default")
      (node (ref "U1") (pin "3") (pinfunction "NC_3") (pintype "passive"))
    )
    (net (code "178") (name "unconnected-(U1-NC-Pad18)") (class "Default")
      (node (ref "U1") (pin "18") (pinfunction "NC_18") (pintype "passive"))
    )
    (net (code "179") (name "unconnected-(U5-EN_B-Pad14)") (class "Default")
      (node (ref "U5") (pin "14") (pinfunction "EN_B_14") (pintype "input"))
    )
    (net (code "180") (name "unconnected-(U5-NC-Pad3)") (class "Default")
      (node (ref "U5") (pin "3") (pinfunction "NC_3") (pintype "passive"))
    )
    (net (code "181") (name "unconnected-(U5-NC-Pad18)") (class "Default")
      (node (ref "U5") (pin "18") (pinfunction "NC_18") (pintype "passive"))
    )
    (net (code "182") (name "unconnected-(U5-OUT3-Pad16)") (class "Default")
      (node (ref "U5") (pin "16") (pinfunction "OUT3_16") (pintype "output"))
    )
    (net (code "183") (name "unconnected-(U5-OUT4-Pad17)") (class "Default")
      (node (ref "U5") (pin "17") (pinfunction "OUT4_17") (pintype "output"))
    )
  )
)
